# module_6_MIC.net
KiCad netlist of a schematic drawn in Altium Designer
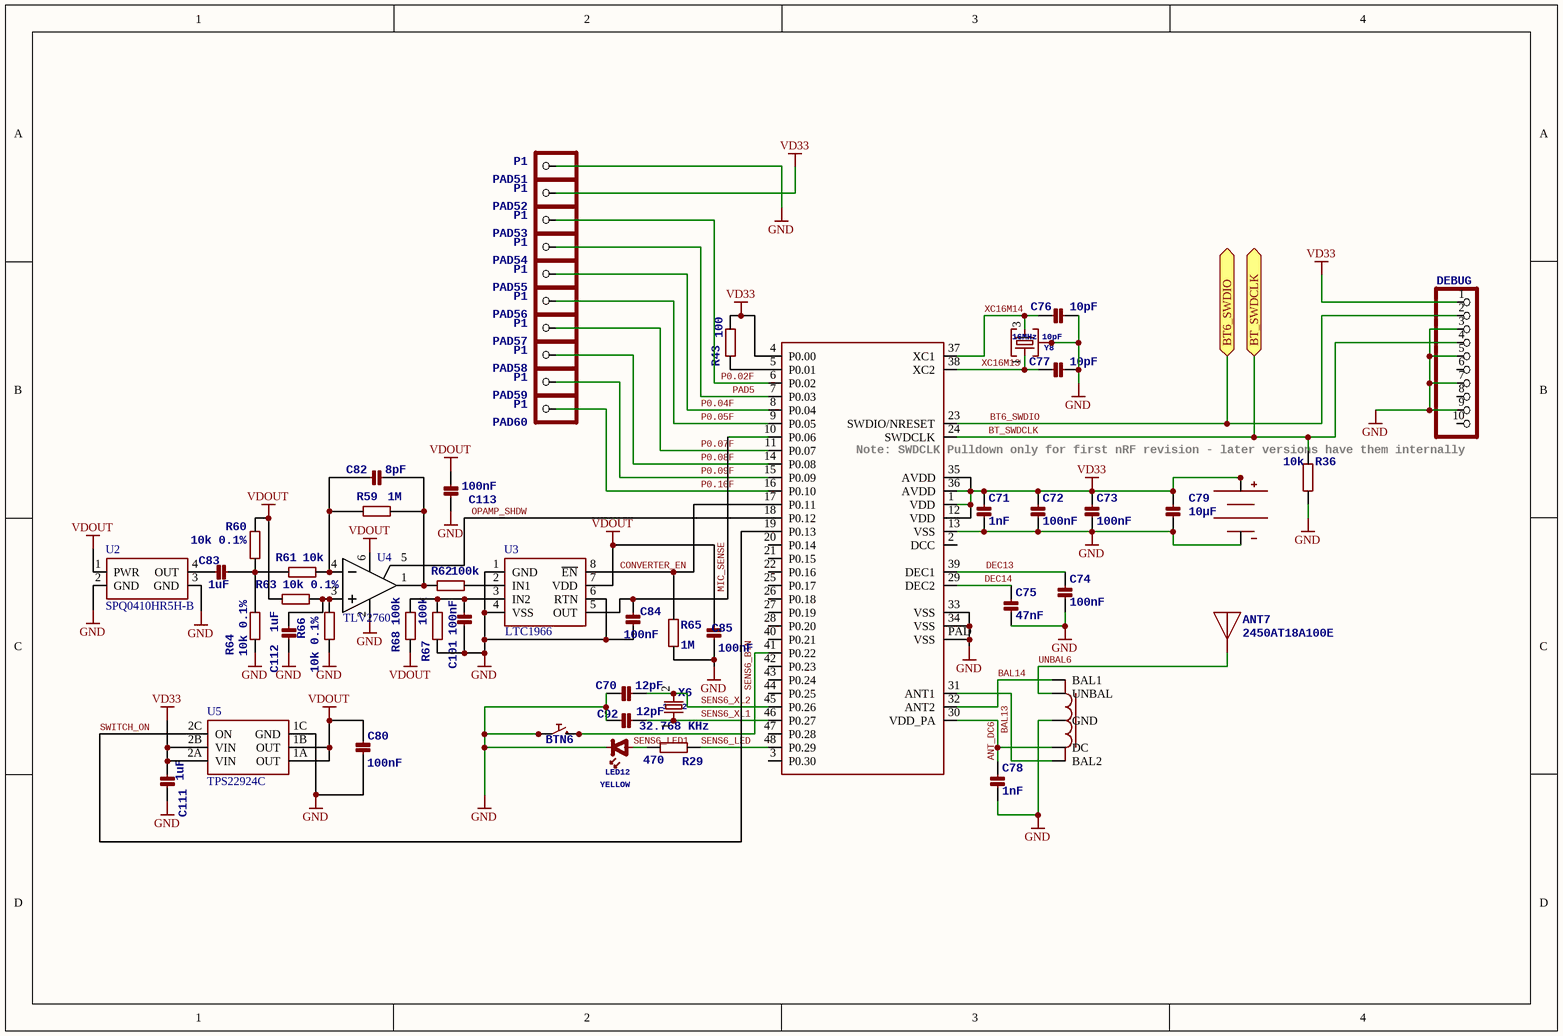
[diagram p0: module 6_MIC.SchDoc]

(export (version "E")
  (design (tool "Eeschema 10.0.6"))
  (components
    (comp (ref "ANT7")
      (value "2450AT18A100E")
      (footprint "1206_MINIMELF_COMBO")
      (description "2.45 GHz Antenna")
      (libsource (lib "WunderBar_v101") (part "ANTENNA_MONOPOLE1206"))
    )
    (comp (ref "BALUN6")
      (value "2450BM14A0002T")
      (footprint "6-PIN-0603")
      (description "2.45 GHz Impedance Matched Balun-Filter")
      (libsource (lib "WunderBar_v101") (part "BALUN"))
    )
    (comp (ref "BAT3")
      (value "BATTERYBK-912")
      (footprint "BK-912")
      (description "Coin battery holder")
      (libsource (lib "WunderBar_v101") (part "BATTERYBK-912"))
    )
    (comp (ref "BT6")
      (value "NRF51822QFN48")
      (footprint "QFN48_EP")
      (description "Nordic Bluetooth 4.0 low energy modul")
      (libsource (lib "WunderBar_v101") (part "NRF51822QFN48"))
    )
    (comp (ref "BTN6")
      (value "Tact Sw 4.6x2.8")
      (footprint "CK-KMR2")
      (description "Push button")
      (libsource (lib "WunderBar_v101") (part "PUSHBUTTONKMR2XX"))
    )
    (comp (ref "C70")
      (value "12pF")
      (footprint "0402")
      (description "Ceramic Capacitors")
      (libsource (lib "") (part "CAP_CERAMIC0402_1"))
    )
    (comp (ref "C71")
      (value "1nF")
      (footprint "0402")
      (description "Ceramic Capacitors")
      (libsource (lib "") (part "CAP_CERAMIC0402_2"))
    )
    (comp (ref "C72")
      (value "100nF")
      (footprint "0402")
      (description "Ceramic Capacitors")
      (libsource (lib "") (part "CAP_CERAMIC0402_2"))
    )
    (comp (ref "C73")
      (value "100nF")
      (footprint "0402")
      (description "Ceramic Capacitors")
      (libsource (lib "") (part "CAP_CERAMIC0402_2"))
    )
    (comp (ref "C74")
      (value "100nF")
      (footprint "0402")
      (description "Ceramic Capacitors")
      (libsource (lib "") (part "CAP_CERAMIC0402_2"))
    )
    (comp (ref "C75")
      (value "47nF")
      (footprint "0402")
      (description "Ceramic Capacitors")
      (libsource (lib "") (part "CAP_CERAMIC0402_2"))
    )
    (comp (ref "C76")
      (value "10pF")
      (footprint "0402")
      (description "Ceramic Capacitors")
      (libsource (lib "") (part "CAP_CERAMIC0402_1"))
    )
    (comp (ref "C77")
      (value "10pF")
      (footprint "0402")
      (description "Ceramic Capacitors")
      (libsource (lib "") (part "CAP_CERAMIC0402_1"))
    )
    (comp (ref "C78")
      (value "1nF")
      (footprint "0402")
      (description "Ceramic Capacitors")
      (libsource (lib "") (part "CAP_CERAMIC0402_2"))
    )
    (comp (ref "C79")
      (value "10µF")
      (footprint "0603")
      (description "Ceramic Capacitor")
      (libsource (lib "WunderBar_v101") (part "CAP_CERAMIC0603"))
    )
    (comp (ref "C80")
      (value "100nF")
      (footprint "0402")
      (description "Ceramic Capacitors")
      (libsource (lib "WunderBar_v101") (part "CAP_CERAMIC0402"))
    )
    (comp (ref "C82")
      (value "8pF")
      (footprint "0402")
      (description "Ceramic Capacitors")
      (libsource (lib "") (part "CAP_CERAMIC0402_1"))
    )
    (comp (ref "C83")
      (value "1uF")
      (footprint "0402")
      (description "Ceramic Capacitors")
      (libsource (lib "") (part "CAP_CERAMIC0402_3"))
    )
    (comp (ref "C84")
      (value "100nF")
      (footprint "0402")
      (description "Ceramic Capacitors")
      (libsource (lib "WunderBar_v101") (part "CAP_CERAMIC0402"))
    )
    (comp (ref "C85")
      (value "100nF")
      (footprint "0402")
      (description "Ceramic Capacitors")
      (libsource (lib "WunderBar_v101") (part "CAP_CERAMIC0402"))
    )
    (comp (ref "C92")
      (value "12pF")
      (footprint "0402")
      (description "Ceramic Capacitors")
      (libsource (lib "") (part "CAP_CERAMIC0402_1"))
    )
    (comp (ref "C101")
      (value "100nF")
      (footprint "0402")
      (description "Ceramic Capacitors")
      (libsource (lib "WunderBar_v101") (part "CAP_CERAMIC0402"))
    )
    (comp (ref "C111")
      (value "1uF")
      (footprint "0402")
      (description "Ceramic Capacitors")
      (libsource (lib "") (part "CAP_CERAMIC0402_2"))
    )
    (comp (ref "C112")
      (value "1uF")
      (footprint "0402")
      (description "Ceramic Capacitors")
      (libsource (lib "WunderBar_v101") (part "CAP_CERAMIC0402"))
    )
    (comp (ref "C113")
      (value "100nF")
      (footprint "0402")
      (description "Ceramic Capacitors")
      (libsource (lib "WunderBar_v101") (part "CAP_CERAMIC0402"))
    )
    (comp (ref "DEBUG6")
      (value "DEBUG")
      (footprint "2X05_SMT")
      (description "cortex DEBUG connector")
      (libsource (lib "WunderBar_v101") (part "HEADER-2X5SMD-1.27MM"))
    )
    (comp (ref "LED12")
      (value "YELLOW")
      (footprint "0402_POLAR")
      (description "LED common")
      (libsource (lib "WunderBar_v101") (part "LED0402"))
    )
    (comp (ref "PAD51")
      (value "P1")
      (footprint "PCB_MEDIUM_RECT_PAD")
      (description "<b>PIN HEADER</b>")
      (libsource (lib "WunderBar_v101") (part "HEADER-1X1SMD_MEDIUM"))
    )
    (comp (ref "PAD52")
      (value "P1")
      (footprint "PCB_MEDIUM_RECT_PAD")
      (description "<b>PIN HEADER</b>")
      (libsource (lib "WunderBar_v101") (part "HEADER-1X1SMD_MEDIUM"))
    )
    (comp (ref "PAD53")
      (value "P1")
      (footprint "PCB_MEDIUM_RECT_PAD")
      (description "<b>PIN HEADER</b>")
      (libsource (lib "WunderBar_v101") (part "HEADER-1X1SMD_MEDIUM"))
    )
    (comp (ref "PAD54")
      (value "P1")
      (footprint "PCB_MEDIUM_RECT_PAD")
      (description "<b>PIN HEADER</b>")
      (libsource (lib "WunderBar_v101") (part "HEADER-1X1SMD_MEDIUM"))
    )
    (comp (ref "PAD55")
      (value "P1")
      (footprint "PCB_MEDIUM_RECT_PAD")
      (description "<b>PIN HEADER</b>")
      (libsource (lib "WunderBar_v101") (part "HEADER-1X1SMD_MEDIUM"))
    )
    (comp (ref "PAD56")
      (value "P1")
      (footprint "PCB_MEDIUM_RECT_PAD")
      (description "<b>PIN HEADER</b>")
      (libsource (lib "WunderBar_v101") (part "HEADER-1X1SMD_MEDIUM"))
    )
    (comp (ref "PAD57")
      (value "P1")
      (footprint "PCB_MEDIUM_RECT_PAD")
      (description "<b>PIN HEADER</b>")
      (libsource (lib "WunderBar_v101") (part "HEADER-1X1SMD_MEDIUM"))
    )
    (comp (ref "PAD58")
      (value "P1")
      (footprint "PCB_MEDIUM_RECT_PAD")
      (description "<b>PIN HEADER</b>")
      (libsource (lib "WunderBar_v101") (part "HEADER-1X1SMD_MEDIUM"))
    )
    (comp (ref "PAD59")
      (value "P1")
      (footprint "PCB_MEDIUM_RECT_PAD")
      (description "<b>PIN HEADER</b>")
      (libsource (lib "WunderBar_v101") (part "HEADER-1X1SMD_MEDIUM"))
    )
    (comp (ref "PAD60")
      (value "P1")
      (footprint "PCB_MEDIUM_RECT_PAD")
      (description "<b>PIN HEADER</b>")
      (libsource (lib "WunderBar_v101") (part "HEADER-1X1SMD_MEDIUM"))
    )
    (comp (ref "R29")
      (value "470")
      (footprint "0402")
      (description "<B>RESISTOR</B>, European symbol")
      (libsource (lib "WunderBar_v101") (part "R-EU_0402"))
    )
    (comp (ref "R36")
      (value "10k")
      (footprint "0402")
      (description "<B>RESISTOR</B>, European symbol")
      (libsource (lib "WunderBar_v101") (part "R-EU_0402"))
    )
    (comp (ref "R43")
      (value "100")
      (footprint "0402")
      (description "<B>RESISTOR</B>, European symbol")
      (libsource (lib "WunderBar_v101") (part "R-EU_0402"))
    )
    (comp (ref "R59")
      (value "1M")
      (footprint "0603")
      (description "<B>RESISTOR</B>, European symbol")
      (libsource (lib "WunderBar_v101") (part "R-EU_0402"))
    )
    (comp (ref "R60")
      (value "10k 0.1%")
      (footprint "0402")
      (description "<B>RESISTOR</B>, European symbol")
      (libsource (lib "WunderBar_v101") (part "R-EU_0402"))
    )
    (comp (ref "R61")
      (value "10k")
      (footprint "0603")
      (description "<B>RESISTOR</B>, European symbol")
      (libsource (lib "WunderBar_v101") (part "R-EU_0402"))
    )
    (comp (ref "R62")
      (value "100k")
      (footprint "0402")
      (description "<B>RESISTOR</B>, European symbol")
      (libsource (lib "WunderBar_v101") (part "R-EU_0402"))
    )
    (comp (ref "R63")
      (value "10k 0.1%")
      (footprint "0402")
      (description "<B>RESISTOR</B>, European symbol")
      (libsource (lib "WunderBar_v101") (part "R-EU_0402"))
    )
    (comp (ref "R64")
      (value "10k 0.1%")
      (footprint "0402")
      (description "<B>RESISTOR</B>, European symbol")
      (libsource (lib "WunderBar_v101") (part "R-EU_0402"))
    )
    (comp (ref "R65")
      (value "1M")
      (footprint "0402")
      (description "<B>RESISTOR</B>, European symbol")
      (libsource (lib "WunderBar_v101") (part "R-EU_0402"))
    )
    (comp (ref "R66")
      (value "10k 0.1%")
      (footprint "0402")
      (description "<B>RESISTOR</B>, European symbol")
      (libsource (lib "WunderBar_v101") (part "R-EU_0402"))
    )
    (comp (ref "R67")
      (value "100k")
      (footprint "0402")
      (description "<B>RESISTOR</B>, European symbol")
      (libsource (lib "WunderBar_v101") (part "R-EU_0402"))
    )
    (comp (ref "R68")
      (value "100k")
      (footprint "0402")
      (description "<B>RESISTOR</B>, European symbol")
      (libsource (lib "WunderBar_v101") (part "R-EU_0402"))
    )
    (comp (ref "U2")
      (value "SPQ0410HR5H-B")
      (footprint "SPQ0410HR5H-B")
      (description "SPQ0410HR5H-B mic")
      (libsource (lib "WunderBar_v101") (part "SPU0410HR5H-PB"))
    )
    (comp (ref "U3")
      (value "LTC1966")
      (footprint "MSOP-8")
      (description "RMS-to-DC converter")
      (libsource (lib "WunderBar_v101") (part "LTC1966"))
    )
    (comp (ref "U4")
      (value "TLV2760")
      (footprint "DBV-6")
      (description "TI OP-AMP")
      (libsource (lib "WunderBar_v101") (part "TLV2760"))
    )
    (comp (ref "U5")
      (value "TPS22924C")
      (footprint "YZP-6")
      (description "LOAD SWITCH")
      (libsource (lib "WunderBar_v101") (part "TPS22963"))
    )
    (comp (ref "X6")
      (value "32.768 KHz")
      (footprint "1206_MINIMELF_COMBO")
      (description "CL05C120JB5")
      (fields (field (name "1") "1") (field (name "2") "2"))
      (libsource (lib "WunderBar_v101") (part "CRYSTAL1206"))
    )
    (comp (ref "Y8")
      (value "16MHz 10pF")
      (footprint "CRYSTAL25X20")
      (description "16MHz crystal 2.5x2mm")
      (libsource (lib "WunderBar_v101") (part "CRYSTAL_WITH_GROUND25X20"))
    )
  )
  (nets
    (net (code "1") (name "/ANT_DC6") (class "Default")
      (node (ref "BALUN6") (pin "5") (pinfunction "DC_5") (pintype "power_in"))
      (node (ref "BT6") (pin "30") (pinfunction "VDD_PA_30") (pintype "passive"))
      (node (ref "C78") (pin "1") (pinfunction "1_1") (pintype "passive"))
    )
    (net (code "2") (name "/BAL13") (class "Default")
      (node (ref "BALUN6") (pin "4") (pinfunction "BAL2_4") (pintype "passive"))
      (node (ref "BT6") (pin "31") (pinfunction "ANT1_31") (pintype "passive"))
    )
    (net (code "3") (name "/BAL14") (class "Default")
      (node (ref "BALUN6") (pin "3") (pinfunction "BAL1_3") (pintype "passive"))
      (node (ref "BT6") (pin "32") (pinfunction "ANT2_32") (pintype "passive"))
    )
    (net (code "4") (name "/BT6_SWDIO") (class "Default")
      (node (ref "BT6") (pin "23") (pinfunction "SWDIO/NRESET_23") (pintype "passive"))
      (node (ref "DEBUG6") (pin "2") (pinfunction "2_2") (pintype "passive"))
    )
    (net (code "5") (name "/BT_SWDCLK") (class "Default")
      (node (ref "BT6") (pin "24") (pinfunction "SWDCLK_24") (pintype "passive"))
      (node (ref "DEBUG6") (pin "4") (pinfunction "4_4") (pintype "passive"))
      (node (ref "R36") (pin "2") (pinfunction "2_2") (pintype "passive"))
    )
    (net (code "6") (name "/CONVERTER_EN") (class "Default")
      (node (ref "BT6") (pin "17") (pinfunction "P0.11_17") (pintype "passive"))
      (node (ref "R65") (pin "1") (pinfunction "1_1") (pintype "passive"))
      (node (ref "U3") (pin "8") (pinfunction "~{EN}_8") (pintype "passive"))
    )
    (net (code "7") (name "/DEC13") (class "Default")
      (node (ref "BT6") (pin "39") (pinfunction "DEC1_39") (pintype "passive"))
      (node (ref "C74") (pin "1") (pinfunction "1_1") (pintype "passive"))
    )
    (net (code "8") (name "/DEC14") (class "Default")
      (node (ref "BT6") (pin "29") (pinfunction "DEC2_29") (pintype "passive"))
      (node (ref "C75") (pin "1") (pinfunction "1_1") (pintype "passive"))
    )
    (net (code "9") (name "/MIC_SENSE") (class "Default")
      (node (ref "BT6") (pin "10") (pinfunction "P0.06_10") (pintype "passive"))
      (node (ref "C84") (pin "2") (pinfunction "2_2") (pintype "passive"))
      (node (ref "U3") (pin "5") (pinfunction "OUT_5") (pintype "passive"))
    )
    (net (code "10") (name "/OPAMP_SHDW") (class "Default")
      (node (ref "BT6") (pin "18") (pinfunction "P0.12_18") (pintype "passive"))
      (node (ref "U4") (pin "5") (pinfunction "~{SHD}_5") (pintype "passive"))
    )
    (net (code "11") (name "/P0.02F") (class "Default")
      (node (ref "BT6") (pin "6") (pinfunction "P0.02_6") (pintype "passive"))
      (node (ref "PAD53") (pin "1") (pinfunction "1_1") (pintype "passive"))
    )
    (net (code "12") (name "/P0.04F") (class "Default")
      (node (ref "BT6") (pin "8") (pinfunction "P0.04_8") (pintype "passive"))
      (node (ref "PAD55") (pin "1") (pinfunction "1_1") (pintype "passive"))
    )
    (net (code "13") (name "/P0.05F") (class "Default")
      (node (ref "BT6") (pin "9") (pinfunction "P0.05_9") (pintype "passive"))
      (node (ref "PAD56") (pin "1") (pinfunction "1_1") (pintype "passive"))
    )
    (net (code "14") (name "/P0.07F") (class "Default")
      (node (ref "BT6") (pin "11") (pinfunction "P0.07_11") (pintype "passive"))
      (node (ref "PAD57") (pin "1") (pinfunction "1_1") (pintype "passive"))
    )
    (net (code "15") (name "/P0.08F") (class "Default")
      (node (ref "BT6") (pin "14") (pinfunction "P0.08_14") (pintype "passive"))
      (node (ref "PAD58") (pin "1") (pinfunction "1_1") (pintype "passive"))
    )
    (net (code "16") (name "/P0.09F") (class "Default")
      (node (ref "BT6") (pin "15") (pinfunction "P0.09_15") (pintype "passive"))
      (node (ref "PAD59") (pin "1") (pinfunction "1_1") (pintype "passive"))
    )
    (net (code "17") (name "/P0.10F") (class "Default")
      (node (ref "BT6") (pin "16") (pinfunction "P0.10_16") (pintype "passive"))
      (node (ref "PAD60") (pin "1") (pinfunction "1_1") (pintype "passive"))
    )
    (net (code "18") (name "/PAD5") (class "Default")
      (node (ref "BT6") (pin "7") (pinfunction "P0.03_7") (pintype "passive"))
      (node (ref "PAD54") (pin "1") (pinfunction "1_1") (pintype "passive"))
    )
    (net (code "19") (name "/SENS6_BTN") (class "Default")
      (node (ref "BT6") (pin "41") (pinfunction "P0.22_41") (pintype "passive"))
      (node (ref "BTN6") (pin "P3") (pinfunction "3_P3") (pintype "passive"))
      (node (ref "BTN6") (pin "P4") (pinfunction "4_P4") (pintype "passive"))
    )
    (net (code "20") (name "/SENS6_LED") (class "Default")
      (node (ref "BT6") (pin "48") (pinfunction "P0.29_48") (pintype "passive"))
      (node (ref "R29") (pin "1") (pinfunction "1_1") (pintype "passive"))
    )
    (net (code "21") (name "/SENS6_LED1") (class "Default")
      (node (ref "LED12") (pin "A") (pinfunction "ANODE_A") (pintype "passive"))
      (node (ref "R29") (pin "2") (pinfunction "2_2") (pintype "passive"))
    )
    (net (code "22") (name "/SENS6_XL1") (class "Default")
      (node (ref "BT6") (pin "46") (pinfunction "P0.27_46") (pintype "passive"))
      (node (ref "C92") (pin "2") (pinfunction "2_2") (pintype "passive"))
      (node (ref "X6") (pin "1") (pinfunction "1_1") (pintype "passive"))
    )
    (net (code "23") (name "/SENS6_XL2") (class "Default")
      (node (ref "BT6") (pin "45") (pinfunction "P0.26_45") (pintype "passive"))
      (node (ref "C70") (pin "2") (pinfunction "2_2") (pintype "passive"))
      (node (ref "X6") (pin "2") (pinfunction "2_2") (pintype "passive"))
    )
    (net (code "24") (name "/SWITCH_ON") (class "Default")
      (node (ref "BT6") (pin "19") (pinfunction "P0.13_19") (pintype "passive"))
      (node (ref "U5") (pin "2C") (pinfunction "ON_2C") (pintype "power_in"))
    )
    (net (code "25") (name "/UNBAL6") (class "Default")
      (node (ref "ANT7") (pin "1") (pinfunction "ANT_1") (pintype "passive"))
      (node (ref "BALUN6") (pin "1") (pinfunction "UNBAL_1") (pintype "passive"))
    )
    (net (code "26") (name "/XC16M13") (class "Default")
      (node (ref "BT6") (pin "38") (pinfunction "XC2_38") (pintype "passive"))
      (node (ref "C77") (pin "1") (pinfunction "1_1") (pintype "passive"))
      (node (ref "Y8") (pin "1") (pinfunction "1_1") (pintype "passive"))
    )
    (net (code "27") (name "/XC16M14") (class "Default")
      (node (ref "BT6") (pin "37") (pinfunction "XC1_37") (pintype "passive"))
      (node (ref "C76") (pin "1") (pinfunction "1_1") (pintype "passive"))
      (node (ref "Y8") (pin "3") (pinfunction "3_3") (pintype "passive"))
    )
    (net (code "28") (name "GND") (class "Default")
      (node (ref "BALUN6") (pin "2") (pinfunction "GND_2") (pintype "power_in"))
      (node (ref "BAT3") (pin "-") (pinfunction "-_-") (pintype "power_in"))
      (node (ref "BT6") (pin "13") (pinfunction "VSS_13") (pintype "passive"))
      (node (ref "BT6") (pin "33") (pinfunction "VSS_33") (pintype "passive"))
      (node (ref "BT6") (pin "34") (pinfunction "VSS_34") (pintype "passive"))
      (node (ref "BT6") (pin "PAD") (pinfunction "VSS_PAD") (pintype "passive"))
      (node (ref "BTN6") (pin "P1") (pinfunction "1_P1") (pintype "passive"))
      (node (ref "BTN6") (pin "P2") (pinfunction "2_P2") (pintype "passive"))
      (node (ref "C101") (pin "1") (pinfunction "1_1") (pintype "passive"))
      (node (ref "C111") (pin "2") (pinfunction "2_2") (pintype "passive"))
      (node (ref "C112") (pin "1") (pinfunction "1_1") (pintype "passive"))
      (node (ref "C113") (pin "1") (pinfunction "1_1") (pintype "passive"))
      (node (ref "C70") (pin "1") (pinfunction "1_1") (pintype "passive"))
      (node (ref "C71") (pin "2") (pinfunction "2_2") (pintype "passive"))
      (node (ref "C72") (pin "2") (pinfunction "2_2") (pintype "passive"))
      (node (ref "C73") (pin "2") (pinfunction "2_2") (pintype "passive"))
      (node (ref "C74") (pin "2") (pinfunction "2_2") (pintype "passive"))
      (node (ref "C75") (pin "2") (pinfunction "2_2") (pintype "passive"))
      (node (ref "C76") (pin "2") (pinfunction "2_2") (pintype "passive"))
      (node (ref "C77") (pin "2") (pinfunction "2_2") (pintype "passive"))
      (node (ref "C78") (pin "2") (pinfunction "2_2") (pintype "passive"))
      (node (ref "C79") (pin "2") (pinfunction "P2_2") (pintype "passive"))
      (node (ref "C80") (pin "1") (pinfunction "1_1") (pintype "passive"))
      (node (ref "C84") (pin "1") (pinfunction "1_1") (pintype "passive"))
      (node (ref "C85") (pin "1") (pinfunction "1_1") (pintype "passive"))
      (node (ref "C92") (pin "1") (pinfunction "1_1") (pintype "passive"))
      (node (ref "DEBUG6") (pin "3") (pinfunction "3_3") (pintype "passive"))
      (node (ref "DEBUG6") (pin "5") (pinfunction "5_5") (pintype "passive"))
      (node (ref "DEBUG6") (pin "7") (pinfunction "7_7") (pintype "passive"))
      (node (ref "DEBUG6") (pin "9") (pinfunction "9_9") (pintype "passive"))
      (node (ref "LED12") (pin "K") (pinfunction "CATHODE_K") (pintype "passive"))
      (node (ref "PAD51") (pin "1") (pinfunction "1_1") (pintype "passive"))
      (node (ref "R36") (pin "1") (pinfunction "1_1") (pintype "passive"))
      (node (ref "R64") (pin "2") (pinfunction "2_2") (pintype "passive"))
      (node (ref "R65") (pin "2") (pinfunction "2_2") (pintype "passive"))
      (node (ref "R66") (pin "1") (pinfunction "1_1") (pintype "passive"))
      (node (ref "R67") (pin "1") (pinfunction "1_1") (pintype "passive"))
      (node (ref "U2") (pin "2") (pinfunction "GND_2") (pintype "passive"))
      (node (ref "U2") (pin "3") (pinfunction "GND_3") (pintype "power_in"))
      (node (ref "U3") (pin "1") (pinfunction "GND_1") (pintype "power_in"))
      (node (ref "U3") (pin "4") (pinfunction "VSS_4") (pintype "passive"))
      (node (ref "U3") (pin "6") (pinfunction "RTN_6") (pintype "passive"))
      (node (ref "U4") (pin "2") (pinfunction "GND_2") (pintype "passive"))
      (node (ref "U5") (pin "1C") (pinfunction "GND_1C") (pintype "passive"))
      (node (ref "Y8") (pin "2") (pinfunction "2_2") (pintype "power_in"))
      (node (ref "Y8") (pin "4") (pinfunction "4_4") (pintype "power_in"))
    )
    (net (code "29") (name "Net-(BT6-P0.01)") (class "Default")
      (node (ref "BT6") (pin "5") (pinfunction "P0.01_5") (pintype "passive"))
      (node (ref "R43") (pin "2") (pinfunction "2_2") (pintype "passive"))
    )
    (net (code "30") (name "Net-(C83-Pad1)") (class "Default")
      (node (ref "C83") (pin "1") (pinfunction "1_1") (pintype "passive"))
      (node (ref "R60") (pin "2") (pinfunction "2_2") (pintype "passive"))
      (node (ref "R61") (pin "1") (pinfunction "1_1") (pintype "passive"))
      (node (ref "R64") (pin "1") (pinfunction "1_1") (pintype "passive"))
    )
    (net (code "31") (name "Net-(U2-OUT)") (class "Default")
      (node (ref "C83") (pin "2") (pinfunction "2_2") (pintype "passive"))
      (node (ref "U2") (pin "4") (pinfunction "OUT_4") (pintype "passive"))
    )
    (net (code "32") (name "Net-(U3-IN1)") (class "Default")
      (node (ref "R62") (pin "2") (pinfunction "2_2") (pintype "passive"))
      (node (ref "U3") (pin "2") (pinfunction "IN1_2") (pintype "passive"))
    )
    (net (code "33") (name "Net-(U3-IN2)") (class "Default")
      (node (ref "C101") (pin "2") (pinfunction "2_2") (pintype "passive"))
      (node (ref "R67") (pin "2") (pinfunction "2_2") (pintype "passive"))
      (node (ref "R68") (pin "2") (pinfunction "2_2") (pintype "passive"))
      (node (ref "U3") (pin "3") (pinfunction "IN2_3") (pintype "power_in"))
    )
    (net (code "34") (name "Net-(U4-IN+)") (class "Default")
      (node (ref "C112") (pin "2") (pinfunction "2_2") (pintype "passive"))
      (node (ref "R63") (pin "2") (pinfunction "2_2") (pintype "passive"))
      (node (ref "R66") (pin "2") (pinfunction "2_2") (pintype "passive"))
      (node (ref "U4") (pin "3") (pinfunction "IN+_3") (pintype "passive"))
    )
    (net (code "35") (name "Net-(U4-IN-)") (class "Default")
      (node (ref "C82") (pin "1") (pinfunction "1_1") (pintype "passive"))
      (node (ref "R59") (pin "1") (pinfunction "1_1") (pintype "passive"))
      (node (ref "R61") (pin "2") (pinfunction "2_2") (pintype "passive"))
      (node (ref "U4") (pin "4") (pinfunction "IN-_4") (pintype "passive"))
    )
    (net (code "36") (name "Net-(U4-OUT)") (class "Default")
      (node (ref "C82") (pin "2") (pinfunction "2_2") (pintype "passive"))
      (node (ref "R59") (pin "2") (pinfunction "2_2") (pintype "passive"))
      (node (ref "R62") (pin "1") (pinfunction "1_1") (pintype "passive"))
      (node (ref "U4") (pin "1") (pinfunction "OUT_1") (pintype "passive"))
    )
    (net (code "37") (name "VD33") (class "Default")
      (node (ref "BAT3") (pin "+1") (pinfunction "+_+1") (pintype "power_in"))
      (node (ref "BAT3") (pin "+2") (pinfunction "+_+2") (pintype "power_in"))
      (node (ref "BT6") (pin "1") (pinfunction "VDD_1") (pintype "passive"))
      (node (ref "BT6") (pin "12") (pinfunction "VDD_12") (pintype "passive"))
      (node (ref "BT6") (pin "35") (pinfunction "AVDD_35") (pintype "passive"))
      (node (ref "BT6") (pin "36") (pinfunction "AVDD_36") (pintype "passive"))
      (node (ref "BT6") (pin "4") (pinfunction "P0.00_4") (pintype "passive"))
      (node (ref "C111") (pin "1") (pinfunction "1_1") (pintype "passive"))
      (node (ref "C71") (pin "1") (pinfunction "1_1") (pintype "passive"))
      (node (ref "C72") (pin "1") (pinfunction "1_1") (pintype "passive"))
      (node (ref "C73") (pin "1") (pinfunction "1_1") (pintype "passive"))
      (node (ref "C79") (pin "1") (pinfunction "P1_1") (pintype "passive"))
      (node (ref "DEBUG6") (pin "1") (pinfunction "1_1") (pintype "passive"))
      (node (ref "PAD52") (pin "1") (pinfunction "1_1") (pintype "passive"))
      (node (ref "R43") (pin "1") (pinfunction "1_1") (pintype "passive"))
      (node (ref "U5") (pin "2A") (pinfunction "VIN_2A") (pintype "power_in"))
      (node (ref "U5") (pin "2B") (pinfunction "VIN_2B") (pintype "passive"))
    )
    (net (code "38") (name "VDOUT") (class "Default")
      (node (ref "C113") (pin "2") (pinfunction "2_2") (pintype "passive"))
      (node (ref "C80") (pin "2") (pinfunction "2_2") (pintype "passive"))
      (node (ref "C85") (pin "2") (pinfunction "2_2") (pintype "passive"))
      (node (ref "R60") (pin "1") (pinfunction "1_1") (pintype "passive"))
      (node (ref "R63") (pin "1") (pinfunction "1_1") (pintype "passive"))
      (node (ref "R68") (pin "1") (pinfunction "1_1") (pintype "passive"))
      (node (ref "U2") (pin "1") (pinfunction "PWR_1") (pintype "power_in"))
      (node (ref "U3") (pin "7") (pinfunction "VDD_7") (pintype "passive"))
      (node (ref "U4") (pin "6") (pinfunction "V+_6") (pintype "passive"))
      (node (ref "U5") (pin "1A") (pinfunction "OUT_1A") (pintype "passive"))
      (node (ref "U5") (pin "1B") (pinfunction "OUT_1B") (pintype "passive"))
    )
    (net (code "39") (name "unconnected-(BT6-DCC-Pad2)") (class "Default")
      (node (ref "BT6") (pin "2") (pinfunction "DCC_2") (pintype "passive"))
    )
    (net (code "40") (name "unconnected-(BT6-P0.14-Pad20)") (class "Default")
      (node (ref "BT6") (pin "20") (pinfunction "P0.14_20") (pintype "passive"))
    )
    (net (code "41") (name "unconnected-(BT6-P0.15-Pad21)") (class "Default")
      (node (ref "BT6") (pin "21") (pinfunction "P0.15_21") (pintype "passive"))
    )
    (net (code "42") (name "unconnected-(BT6-P0.16-Pad22)") (class "Default")
      (node (ref "BT6") (pin "22") (pinfunction "P0.16_22") (pintype "passive"))
    )
    (net (code "43") (name "unconnected-(BT6-P0.17-Pad25)") (class "Default")
      (node (ref "BT6") (pin "25") (pinfunction "P0.17_25") (pintype "passive"))
    )
    (net (code "44") (name "unconnected-(BT6-P0.18-Pad26)") (class "Default")
      (node (ref "BT6") (pin "26") (pinfunction "P0.18_26") (pintype "passive"))
    )
    (net (code "45") (name "unconnected-(BT6-P0.19-Pad27)") (class "Default")
      (node (ref "BT6") (pin "27") (pinfunction "P0.19_27") (pintype "passive"))
    )
    (net (code "46") (name "unconnected-(BT6-P0.20-Pad28)") (class "Default")
      (node (ref "BT6") (pin "28") (pinfunction "P0.20_28") (pintype "passive"))
    )
    (net (code "47") (name "unconnected-(BT6-P0.21-Pad40)") (class "Default")
      (node (ref "BT6") (pin "40") (pinfunction "P0.21_40") (pintype "passive"))
    )
    (net (code "48") (name "unconnected-(BT6-P0.23-Pad42)") (class "Default")
      (node (ref "BT6") (pin "42") (pinfunction "P0.23_42") (pintype "passive"))
    )
    (net (code "49") (name "unconnected-(BT6-P0.24-Pad43)") (class "Default")
      (node (ref "BT6") (pin "43") (pinfunction "P0.24_43") (pintype "passive"))
    )
    (net (code "50") (name "unconnected-(BT6-P0.25-Pad44)") (class "Default")
      (node (ref "BT6") (pin "44") (pinfunction "P0.25_44") (pintype "passive"))
    )
    (net (code "51") (name "unconnected-(BT6-P0.28-Pad47)") (class "Default")
      (node (ref "BT6") (pin "47") (pinfunction "P0.28_47") (pintype "passive"))
    )
    (net (code "52") (name "unconnected-(BT6-P0.30-Pad3)") (class "Default")
      (node (ref "BT6") (pin "3") (pinfunction "P0.30_3") (pintype "passive"))
    )
    (net (code "53") (name "unconnected-(DEBUG6-Pad6)") (class "Default")
      (node (ref "DEBUG6") (pin "6") (pinfunction "6_6") (pintype "passive"))
    )
    (net (code "54") (name "unconnected-(DEBUG6-Pad8)") (class "Default")
      (node (ref "DEBUG6") (pin "8") (pinfunction "8_8") (pintype "passive"))
    )
    (net (code "55") (name "unconnected-(DEBUG6-Pad10)") (class "Default")
      (node (ref "DEBUG6") (pin "10") (pinfunction "10_10") (pintype "passive"))
    )
  )
)
